# Schematic.net
KiCad netlist of a schematic drawn in Altium Designer
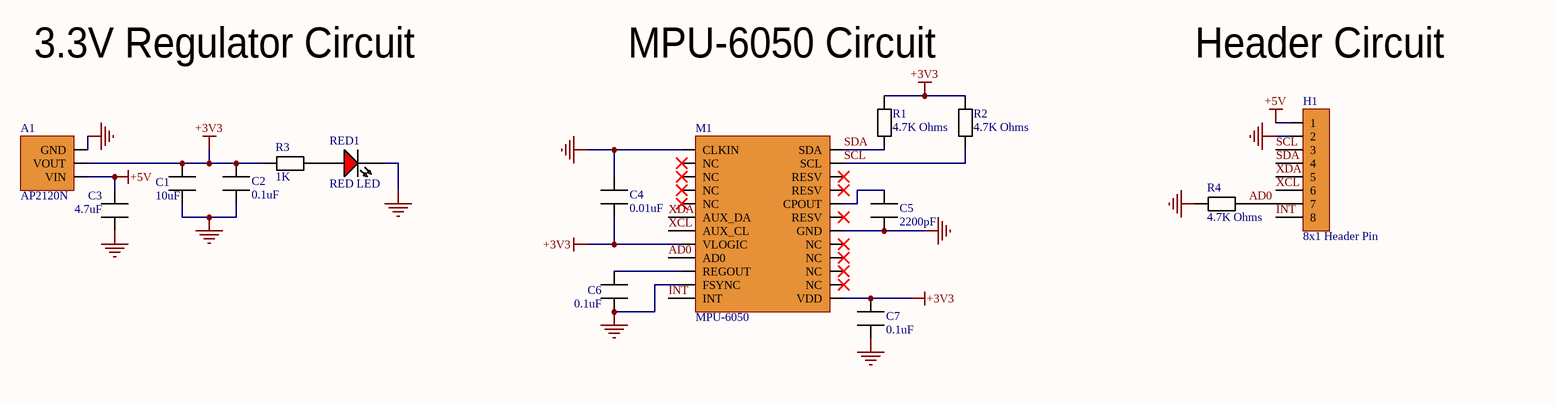
[diagram p0: Schematic.SchDoc]

(export (version "E")
  (design (tool "Eeschema 10.0.6"))
  (components
    (comp (ref "A1")
      (value "AP2120N")
      (footprint "AP2120N")
      (description "IC REG LINEAR 3.3V 150MA SOT23")
      (fields
        (field (name "MANUFACTURER") "Diodes")
        (field (name "MANUFACTURER PART NUMBER") "AP2120N-3.3TRG1")
      )
      (libsource (lib "Schematic Library") (part "AP2120N-3.3TRG1"))
    )
    (comp (ref "C1")
      (value "10uF")
      (footprint "10uF Capacitor")
      (description "Cap Ceramic 10uF 10V X7R 10% Pad SMD 0805 125C T/R")
      (fields
        (field (name "MANUFACTURER") "Murata")
        (field (name "MANUFACTURER PART NUMBER") "GRM21BR71A106KA73K")
      )
      (libsource (lib "Schematic Library") (part "GRM21BR71A106KA73K"))
    )
    (comp (ref "C2")
      (value "0.1uF")
      (footprint "0.1uF")
      (description "CAP CER 0.1UF 100V X7R 0805")
      (fields
        (field (name "MANUFACTURER") "Murata")
        (field (name "MANUFACTURER PART NUMBER") "GCM21BR72A104KA37L")
      )
      (libsource (lib "Schematic Library") (part "GCM21BR72A104KA37L"))
    )
    (comp (ref "C3")
      (value "4.7uF")
      (footprint "4.7uF Capacitor")
      (description "Capacitor: ceramic; 4.7uF; 16V; X7R; ±10%; SMD; 0805; Series: GRM")
      (fields
        (field (name "MANUFACTURER") "Murata")
        (field (name "MANUFACTURER PART NUMBER") "GRM21BR71C475KE51L")
      )
      (libsource (lib "Schematic Library") (part "GRM21BR71C475KE51L"))
    )
    (comp (ref "C4")
      (value "0.01uF")
      (footprint "0.01uF Capacitor")
      (description "MURATA   GCJ21BR72E103KXJ3L   CAP, MLCC, X7R, 10NF, 250V, 0805")
      (fields
        (field (name "MANUFACTURER") "Murata")
        (field (name "MANUFACTURER PART NUMBER") "GCJ21BR72E103KXJ3L")
      )
      (libsource (lib "Schematic Library") (part "GCJ21BR72E103KXJ3L"))
    )
    (comp (ref "C5")
      (value "2200pF")
      (footprint "2200pF Capacitor")
      (description "Multilayer Ceramic Capacitors MLCC - SMD/SMT 0805 2200pF 100volt C0G +/-5%")
      (fields
        (field (name "MANUFACTURER") "Murata")
        (field (name "MANUFACTURER PART NUMBER") "GRM2165C2A222JA01D")
      )
      (libsource (lib "Schematic Library") (part "GRM2165C2A222JA01D"))
    )
    (comp (ref "C6")
      (value "0.1uF")
      (footprint "0.1uF")
      (description "CAP CER 0.1UF 100V X7R 0805")
      (fields
        (field (name "MANUFACTURER") "Murata")
        (field (name "MANUFACTURER PART NUMBER") "GCM21BR72A104KA37L")
      )
      (libsource (lib "Schematic Library") (part "GCM21BR72A104KA37L"))
    )
    (comp (ref "C7")
      (value "0.1uF")
      (footprint "0.1uF")
      (description "CAP CER 0.1UF 100V X7R 0805")
      (fields
        (field (name "MANUFACTURER") "Murata")
        (field (name "MANUFACTURER PART NUMBER") "GCM21BR72A104KA37L")
      )
      (libsource (lib "Schematic Library") (part "GCM21BR72A104KA37L"))
    )
    (comp (ref "H1")
      (value "8x1 Header Pin")
      (footprint "8x1 Header Pin")
      (description "Board-To-Board Connector, Vertical, Wr-Phd Series, Through Hole, Header, 8, 2.54 Mm")
      (fields
        (field (name "MANUFACTURER") "Wurth Electronics")
        (field (name "MANUFACTURER PART NUMBER") "61300811121")
      )
      (libsource (lib "Schematic Library") (part "61300811121"))
    )
    (comp (ref "M1")
      (value "MPU-6050")
      (footprint "MPU-6050")
      (description "INVENSENSE   MPU-6050   GYRO / ACCEL, 6-AXIS, I2C, QFN-24")
      (fields (field (name "MANUFACTURER") "TDK InvenSense"))
      (libsource (lib "Schematic Library") (part "MPU-6050"))
    )
    (comp (ref "R1")
      (value "4.7K Ohms")
      (footprint "4.7K Resistor")
      (description "RES SMD 4.7 OHM 1% 1/4W 0805")
      (fields
        (field (name "MANUFACTURER") "Stackpole Electronics")
        (field (name "MANUFACTURER PART NUMBER") "RNCP0805FTD4R70")
      )
      (libsource (lib "Schematic Library") (part "RNCP0805FTD4R70"))
    )
    (comp (ref "R2")
      (value "4.7K Ohms")
      (footprint "4.7K Resistor")
      (description "RES SMD 4.7 OHM 1% 1/4W 0805")
      (fields
        (field (name "MANUFACTURER") "Stackpole Electronics")
        (field (name "MANUFACTURER PART NUMBER") "RNCP0805FTD4R70")
      )
      (libsource (lib "Schematic Library") (part "RNCP0805FTD4R70"))
    )
    (comp (ref "R3")
      (value "1K")
      (footprint "1K Resistor")
      (description "RES 1K OHM 1% 1/4W 0805")
      (fields
        (field (name "MANUFACTURER") "Stackpole Electronics")
        (field (name "MANUFACTURER PART NUMBER") "RNCP0805FTD1K00")
      )
      (libsource (lib "Schematic Library") (part "RNCP0805FTD1K00"))
    )
    (comp (ref "R4")
      (value "4.7K Ohms")
      (footprint "4.7K Resistor")
      (description "RES SMD 4.7 OHM 1% 1/4W 0805")
      (fields
        (field (name "MANUFACTURER") "Stackpole Electronics")
        (field (name "MANUFACTURER PART NUMBER") "RNCP0805FTD4R70")
      )
      (libsource (lib "Schematic Library") (part "RNCP0805FTD4R70"))
    )
    (comp (ref "RED1")
      (value "RED LED")
      (footprint "Red LED")
      (description "SMD LED red 2.4 V 0805, 150080RS75000, Würth Elektronik")
      (fields
        (field (name "MANUFACTURER") "Wurth Electronics")
        (field (name "MANUFACTURER PART NUMBER") "150080RS75000")
      )
      (libsource (lib "Schematic Library") (part "150080RS75000"))
    )
  )
  (nets
    (net (code "1") (name "+3V3") (class "Default")
      (node (ref "A1") (pin "2") (pinfunction "VOUT_2") (pintype "passive"))
      (node (ref "C1") (pin "2") (pinfunction "2_2") (pintype "passive"))
      (node (ref "C2") (pin "2") (pinfunction "2_2") (pintype "passive"))
      (node (ref "C4") (pin "1") (pinfunction "1_1") (pintype "passive"))
      (node (ref "C7") (pin "2") (pinfunction "2_2") (pintype "passive"))
      (node (ref "M1") (pin "13") (pinfunction "VDD_13") (pintype "passive"))
      (node (ref "M1") (pin "8") (pinfunction "VLOGIC_8") (pintype "passive"))
      (node (ref "R1") (pin "2") (pinfunction "2_2") (pintype "passive"))
      (node (ref "R2") (pin "2") (pinfunction "2_2") (pintype "passive"))
      (node (ref "R3") (pin "1") (pinfunction "1_1") (pintype "passive"))
    )
    (net (code "2") (name "+5V") (class "Default")
      (node (ref "A1") (pin "3") (pinfunction "VIN_3") (pintype "passive"))
      (node (ref "C3") (pin "2") (pinfunction "2_2") (pintype "passive"))
      (node (ref "H1") (pin "1") (pinfunction "1_1") (pintype "passive"))
    )
    (net (code "3") (name "/AD0") (class "Default")
      (node (ref "H1") (pin "7") (pinfunction "7_7") (pintype "passive"))
      (node (ref "M1") (pin "9") (pinfunction "AD0_9") (pintype "passive"))
      (node (ref "R4") (pin "2") (pinfunction "2_2") (pintype "passive"))
    )
    (net (code "4") (name "/INT") (class "Default")
      (node (ref "H1") (pin "8") (pinfunction "8_8") (pintype "passive"))
      (node (ref "M1") (pin "12") (pinfunction "INT_12") (pintype "passive"))
    )
    (net (code "5") (name "/SCL") (class "Default")
      (node (ref "H1") (pin "3") (pinfunction "3_3") (pintype "passive"))
      (node (ref "M1") (pin "23") (pinfunction "SCL_23") (pintype "passive"))
      (node (ref "R2") (pin "1") (pinfunction "1_1") (pintype "passive"))
    )
    (net (code "6") (name "/SDA") (class "Default")
      (node (ref "H1") (pin "4") (pinfunction "4_4") (pintype "passive"))
      (node (ref "M1") (pin "24") (pinfunction "SDA_24") (pintype "passive"))
      (node (ref "R1") (pin "1") (pinfunction "1_1") (pintype "passive"))
    )
    (net (code "7") (name "/XCL") (class "Default")
      (node (ref "H1") (pin "6") (pinfunction "6_6") (pintype "passive"))
      (node (ref "M1") (pin "7") (pinfunction "AUX_CL_7") (pintype "passive"))
    )
    (net (code "8") (name "/XDA") (class "Default")
      (node (ref "H1") (pin "5") (pinfunction "5_5") (pintype "passive"))
      (node (ref "M1") (pin "6") (pinfunction "AUX_DA_6") (pintype "passive"))
    )
    (net (code "9") (name "GND") (class "Default")
      (node (ref "A1") (pin "1") (pinfunction "GND_1") (pintype "passive"))
      (node (ref "C1") (pin "1") (pinfunction "1_1") (pintype "passive"))
      (node (ref "C2") (pin "1") (pinfunction "1_1") (pintype "passive"))
      (node (ref "C3") (pin "1") (pinfunction "1_1") (pintype "passive"))
      (node (ref "C4") (pin "2") (pinfunction "2_2") (pintype "passive"))
      (node (ref "C5") (pin "1") (pinfunction "1_1") (pintype "passive"))
      (node (ref "C6") (pin "1") (pinfunction "1_1") (pintype "passive"))
      (node (ref "C7") (pin "1") (pinfunction "1_1") (pintype "passive"))
      (node (ref "H1") (pin "2") (pinfunction "2_2") (pintype "passive"))
      (node (ref "M1") (pin "1") (pinfunction "CLKIN_1") (pintype "passive"))
      (node (ref "M1") (pin "11") (pinfunction "FSYNC_11") (pintype "passive"))
      (node (ref "M1") (pin "18") (pinfunction "GND_18") (pintype "passive"))
      (node (ref "R4") (pin "1") (pinfunction "1_1") (pintype "passive"))
      (node (ref "RED1") (pin "1") (pinfunction "1_1") (pintype "passive"))
    )
    (net (code "10") (name "Net-(M1-CPOUT)") (class "Default")
      (node (ref "C5") (pin "2") (pinfunction "2_2") (pintype "passive"))
      (node (ref "M1") (pin "20") (pinfunction "CPOUT_20") (pintype "passive"))
    )
    (net (code "11") (name "Net-(M1-REGOUT)") (class "Default")
      (node (ref "C6") (pin "2") (pinfunction "2_2") (pintype "passive"))
      (node (ref "M1") (pin "10") (pinfunction "REGOUT_10") (pintype "passive"))
    )
    (net (code "12") (name "Net-(R3-Pad2)") (class "Default")
      (node (ref "R3") (pin "2") (pinfunction "2_2") (pintype "passive"))
      (node (ref "RED1") (pin "2") (pinfunction "2_2") (pintype "passive"))
    )
    (net (code "13") (name "unconnected-(M1-NC-Pad2)") (class "Default")
      (node (ref "M1") (pin "2") (pinfunction "NC_2") (pintype "passive+no_connect"))
    )
    (net (code "14") (name "unconnected-(M1-NC-Pad3)") (class "Default")
      (node (ref "M1") (pin "3") (pinfunction "NC_3") (pintype "passive+no_connect"))
    )
    (net (code "15") (name "unconnected-(M1-NC-Pad4)") (class "Default")
      (node (ref "M1") (pin "4") (pinfunction "NC_4") (pintype "passive+no_connect"))
    )
    (net (code "16") (name "unconnected-(M1-NC-Pad5)") (class "Default")
      (node (ref "M1") (pin "5") (pinfunction "NC_5") (pintype "passive+no_connect"))
    )
    (net (code "17") (name "unconnected-(M1-NC-Pad14)") (class "Default")
      (node (ref "M1") (pin "14") (pinfunction "NC_14") (pintype "passive+no_connect"))
    )
    (net (code "18") (name "unconnected-(M1-NC-Pad15)") (class "Default")
      (node (ref "M1") (pin "15") (pinfunction "NC_15") (pintype "passive+no_connect"))
    )
    (net (code "19") (name "unconnected-(M1-NC-Pad16)") (class "Default")
      (node (ref "M1") (pin "16") (pinfunction "NC_16") (pintype "passive+no_connect"))
    )
    (net (code "20") (name "unconnected-(M1-NC-Pad17)") (class "Default")
      (node (ref "M1") (pin "17") (pinfunction "NC_17") (pintype "passive+no_connect"))
    )
    (net (code "21") (name "unconnected-(M1-RESV-Pad19)") (class "Default")
      (node (ref "M1") (pin "19") (pinfunction "RESV_19") (pintype "passive+no_connect"))
    )
    (net (code "22") (name "unconnected-(M1-RESV-Pad21)") (class "Default")
      (node (ref "M1") (pin "21") (pinfunction "RESV_21") (pintype "passive+no_connect"))
    )
    (net (code "23") (name "unconnected-(M1-RESV-Pad22)") (class "Default")
      (node (ref "M1") (pin "22") (pinfunction "RESV_22") (pintype "passive+no_connect"))
    )
  )
)
